# ARM_PDU.net
KiCad netlist of a schematic drawn in EAGLE
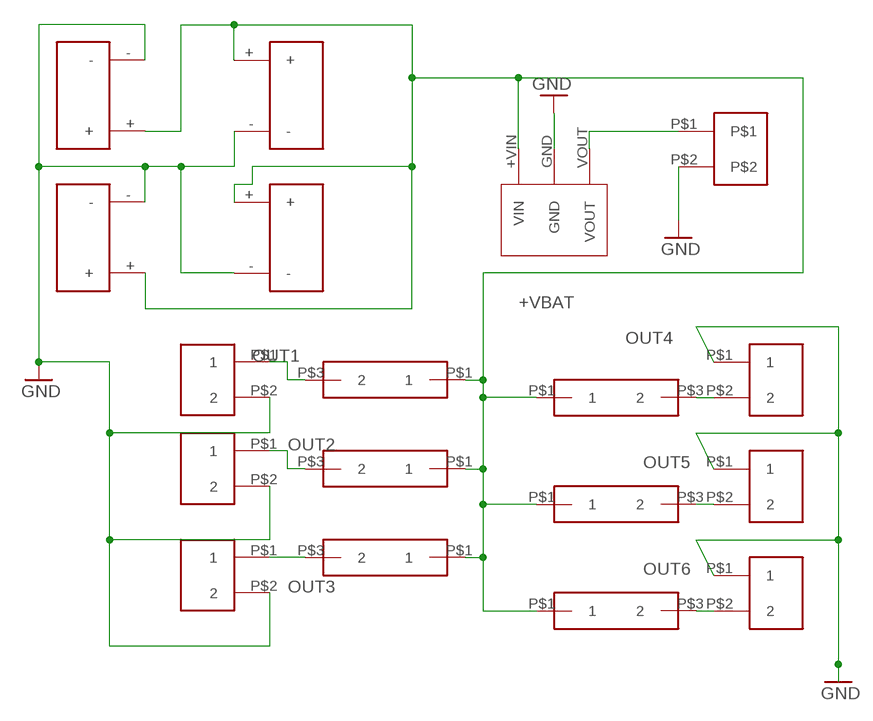
[diagram p0: schematic, sheet 1]

(export (version "E")
  (design (tool "Eeschema 10.0.6"))
  (components
    (comp (ref "U$1")
      (value "20A_FUSE_HOLDER")
      (footprint "eagle-import:20A_FUSE_HOLDER")
      (libsource (lib "eagle-import") (part "20A_FUSE_HOLDER"))
    )
    (comp (ref "U$2")
      (value "20A_FUSE_HOLDER")
      (footprint "eagle-import:20A_FUSE_HOLDER")
      (libsource (lib "eagle-import") (part "20A_FUSE_HOLDER"))
    )
    (comp (ref "U$3")
      (value "20A_FUSE_HOLDER")
      (footprint "eagle-import:20A_FUSE_HOLDER")
      (libsource (lib "eagle-import") (part "20A_FUSE_HOLDER"))
    )
    (comp (ref "U$4")
      (value "PP45_HOR_2BOT")
      (footprint "eagle-import:PP45_HOR_2BOT")
      (libsource (lib "eagle-import") (part "PP45_HOR_2BOT"))
    )
    (comp (ref "U$5")
      (value "PP45_HOR_2BOT")
      (footprint "eagle-import:PP45_HOR_2BOT")
      (libsource (lib "eagle-import") (part "PP45_HOR_2BOT"))
    )
    (comp (ref "U$6")
      (value "PP45_HOR_2BOT")
      (footprint "eagle-import:PP45_HOR_2BOT")
      (libsource (lib "eagle-import") (part "PP45_HOR_2BOT"))
    )
    (comp (ref "U$7")
      (value "PP45_HOR_2BOT")
      (footprint "eagle-import:PP45_HOR_2BOT")
      (libsource (lib "eagle-import") (part "PP45_HOR_2BOT"))
    )
    (comp (ref "U$8")
      (value "AMP-MTE-2MALE")
      (footprint "eagle-import:AMP-MTE-2MALE")
      (libsource (lib "eagle-import") (part "AMP-MTE-2MALE"))
    )
    (comp (ref "U$9")
      (value "R-78E3.3-0.5")
      (footprint "eagle-import:R-78E3.3-0.5")
      (libsource (lib "eagle-import") (part "R-78E3.3-0.5"))
    )
    (comp (ref "U$10")
      (value "2PIN_5MM")
      (footprint "eagle-import:2PIN_5MM")
      (libsource (lib "eagle-import") (part "2PIN_5MM"))
    )
    (comp (ref "U$11")
      (value "2PIN_5MM")
      (footprint "eagle-import:2PIN_5MM")
      (libsource (lib "eagle-import") (part "2PIN_5MM"))
    )
    (comp (ref "U$12")
      (value "2PIN_5MM")
      (footprint "eagle-import:2PIN_5MM")
      (libsource (lib "eagle-import") (part "2PIN_5MM"))
    )
    (comp (ref "U$13")
      (value "2PIN_5MM")
      (footprint "eagle-import:2PIN_5MM")
      (libsource (lib "eagle-import") (part "2PIN_5MM"))
    )
    (comp (ref "U$14")
      (value "20A_FUSE_HOLDER")
      (footprint "eagle-import:20A_FUSE_HOLDER")
      (libsource (lib "eagle-import") (part "20A_FUSE_HOLDER"))
    )
    (comp (ref "U$15")
      (value "20A_FUSE_HOLDER")
      (footprint "eagle-import:20A_FUSE_HOLDER")
      (libsource (lib "eagle-import") (part "20A_FUSE_HOLDER"))
    )
    (comp (ref "U$16")
      (value "20A_FUSE_HOLDER")
      (footprint "eagle-import:20A_FUSE_HOLDER")
      (libsource (lib "eagle-import") (part "20A_FUSE_HOLDER"))
    )
    (comp (ref "U$17")
      (value "2PIN_5MM")
      (footprint "eagle-import:2PIN_5MM")
      (libsource (lib "eagle-import") (part "2PIN_5MM"))
    )
    (comp (ref "U$18")
      (value "2PIN_5MM")
      (footprint "eagle-import:2PIN_5MM")
      (libsource (lib "eagle-import") (part "2PIN_5MM"))
    )
  )
  (nets
    (net (code "1") (name "/+VBAT") (class "Default")
      (node (ref "U$1") (pin "P$1") (pinfunction "1_P$1") (pintype "bidirectional"))
      (node (ref "U$14") (pin "P$1") (pinfunction "1_P$1") (pintype "bidirectional"))
      (node (ref "U$15") (pin "P$1") (pinfunction "1_P$1") (pintype "bidirectional"))
      (node (ref "U$16") (pin "P$1") (pinfunction "1_P$1") (pintype "bidirectional"))
      (node (ref "U$2") (pin "P$1") (pinfunction "1_P$1") (pintype "bidirectional"))
      (node (ref "U$3") (pin "P$1") (pinfunction "1_P$1") (pintype "bidirectional"))
      (node (ref "U$4") (pin "+") (pinfunction "+_+") (pintype "bidirectional"))
      (node (ref "U$5") (pin "+") (pinfunction "+_+") (pintype "bidirectional"))
      (node (ref "U$6") (pin "+") (pinfunction "+_+") (pintype "bidirectional"))
      (node (ref "U$7") (pin "+") (pinfunction "+_+") (pintype "bidirectional"))
      (node (ref "U$9") (pin "+VIN") (pinfunction "VIN_+VIN") (pintype "bidirectional"))
    )
    (net (code "2") (name "/OUT1") (class "Default")
      (node (ref "U$1") (pin "P$3") (pinfunction "2_P$3") (pintype "bidirectional"))
      (node (ref "U$13") (pin "P$1") (pinfunction "1_P$1") (pintype "bidirectional"))
    )
    (net (code "3") (name "/OUT2") (class "Default")
      (node (ref "U$17") (pin "P$1") (pinfunction "1_P$1") (pintype "bidirectional"))
      (node (ref "U$2") (pin "P$3") (pinfunction "2_P$3") (pintype "bidirectional"))
    )
    (net (code "4") (name "/OUT3") (class "Default")
      (node (ref "U$18") (pin "P$1") (pinfunction "1_P$1") (pintype "bidirectional"))
      (node (ref "U$3") (pin "P$3") (pinfunction "2_P$3") (pintype "bidirectional"))
    )
    (net (code "5") (name "/OUT4") (class "Default")
      (node (ref "U$10") (pin "P$2") (pinfunction "2_P$2") (pintype "bidirectional"))
      (node (ref "U$16") (pin "P$3") (pinfunction "2_P$3") (pintype "bidirectional"))
    )
    (net (code "6") (name "/OUT5") (class "Default")
      (node (ref "U$11") (pin "P$2") (pinfunction "2_P$2") (pintype "bidirectional"))
      (node (ref "U$15") (pin "P$3") (pinfunction "2_P$3") (pintype "bidirectional"))
    )
    (net (code "7") (name "/OUT6") (class "Default")
      (node (ref "U$12") (pin "P$2") (pinfunction "2_P$2") (pintype "bidirectional"))
      (node (ref "U$14") (pin "P$3") (pinfunction "2_P$3") (pintype "bidirectional"))
    )
    (net (code "8") (name "GND") (class "Default")
      (node (ref "U$10") (pin "P$1") (pinfunction "1_P$1") (pintype "bidirectional"))
      (node (ref "U$11") (pin "P$1") (pinfunction "1_P$1") (pintype "bidirectional"))
      (node (ref "U$12") (pin "P$1") (pinfunction "1_P$1") (pintype "bidirectional"))
      (node (ref "U$13") (pin "P$2") (pinfunction "2_P$2") (pintype "bidirectional"))
      (node (ref "U$17") (pin "P$2") (pinfunction "2_P$2") (pintype "bidirectional"))
      (node (ref "U$18") (pin "P$2") (pinfunction "2_P$2") (pintype "bidirectional"))
      (node (ref "U$4") (pin "-") (pinfunction "-_-") (pintype "bidirectional"))
      (node (ref "U$5") (pin "-") (pinfunction "-_-") (pintype "bidirectional"))
      (node (ref "U$6") (pin "-") (pinfunction "-_-") (pintype "bidirectional"))
      (node (ref "U$7") (pin "-") (pinfunction "-_-") (pintype "bidirectional"))
      (node (ref "U$8") (pin "P$2") (pinfunction "P$2_P$2") (pintype "bidirectional"))
      (node (ref "U$9") (pin "GND") (pinfunction "GND_GND") (pintype "bidirectional"))
    )
    (net (code "9") (name "Net-(U$8-PadP$1)") (class "Default")
      (node (ref "U$8") (pin "P$1") (pinfunction "P$1_P$1") (pintype "bidirectional"))
      (node (ref "U$9") (pin "VOUT") (pinfunction "VOUT_VOUT") (pintype "bidirectional"))
    )
  )
)
